# FMB-POWER.net
KiCad netlist of a schematic drawn in Altium Designer
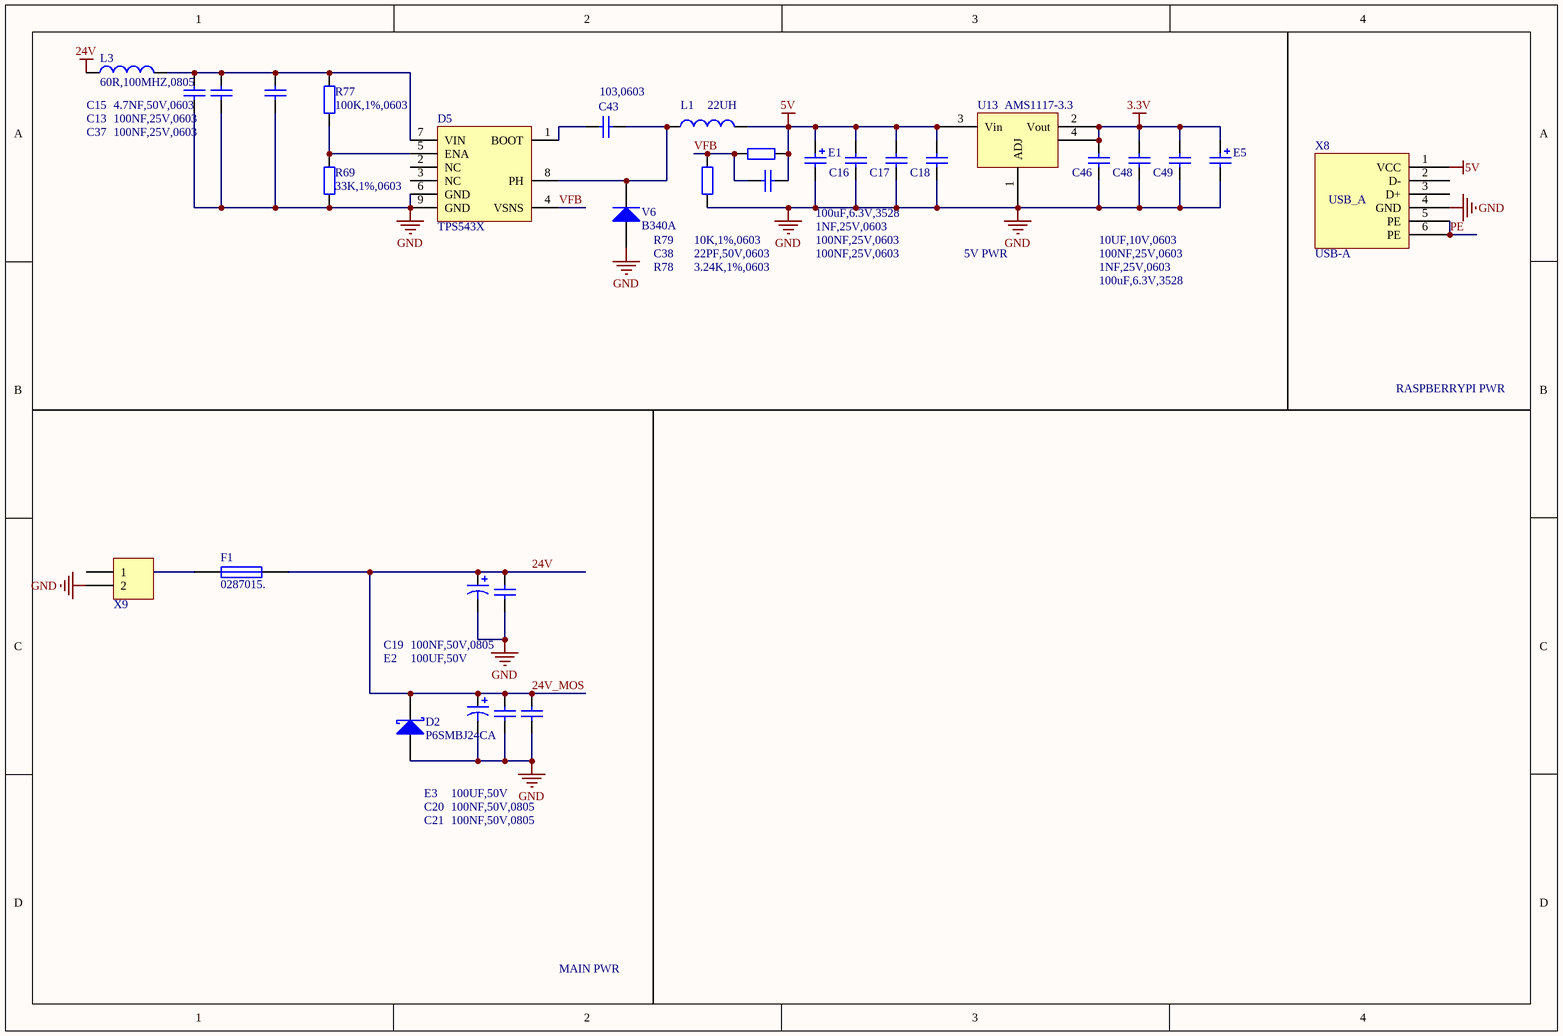
[diagram p0: FMB-POWER.SchDoc]

(export (version "E")
  (design (tool "Eeschema 10.0.6"))
  (components
    (comp (ref "C13")
      (value "100NF,25V,0603")
      (footprint "RC0603")
      (description "Capacitor")
      (fields (field (name "PUBLISHER") "Altium Limited"))
      (libsource (lib "Miscellaneous Devices") (part "Cap"))
    )
    (comp (ref "C15")
      (value "4.7NF,50V,0603")
      (footprint "RC0603")
      (description "Capacitor")
      (fields (field (name "PUBLISHER") "Altium Limited"))
      (libsource (lib "Miscellaneous Devices") (part "Cap"))
    )
    (comp (ref "C16")
      (value "1NF,25V,0603")
      (footprint "RC0603")
      (description "Capacitor")
      (fields (field (name "PUBLISHER") "Altium Limited"))
      (libsource (lib "Miscellaneous Devices") (part "Cap"))
    )
    (comp (ref "C17")
      (value "100NF,25V,0603")
      (footprint "RC0603")
      (description "Capacitor")
      (fields (field (name "PUBLISHER") "Altium Limited"))
      (libsource (lib "Miscellaneous Devices") (part "Cap"))
    )
    (comp (ref "C18")
      (value "100NF,25V,0603")
      (footprint "RC0603")
      (description "Capacitor")
      (fields (field (name "PUBLISHER") "Altium Limited"))
      (libsource (lib "Miscellaneous Devices") (part "Cap"))
    )
    (comp (ref "C19")
      (value "100NF,50V,0805")
      (footprint "RC0805")
      (description "Capacitor")
      (fields (field (name "PUBLISHER") "Altium Limited"))
      (libsource (lib "Miscellaneous Devices") (part "Cap"))
    )
    (comp (ref "C20")
      (value "100NF,50V,0805")
      (footprint "RC0805")
      (description "Capacitor")
      (fields (field (name "PUBLISHER") "Altium Limited"))
      (libsource (lib "Miscellaneous Devices") (part "Cap"))
    )
    (comp (ref "C21")
      (value "100NF,50V,0805")
      (footprint "RC0805")
      (description "Capacitor")
      (fields (field (name "PUBLISHER") "Altium Limited"))
      (libsource (lib "Miscellaneous Devices") (part "Cap"))
    )
    (comp (ref "C37")
      (value "100NF,25V,0603")
      (footprint "RC0603")
      (description "Capacitor")
      (fields (field (name "PUBLISHER") "Altium Limited"))
      (libsource (lib "Miscellaneous Devices") (part "Cap"))
    )
    (comp (ref "C38")
      (value "22PF,50V,0603")
      (footprint "RC0603")
      (description "Capacitor")
      (fields (field (name "PUBLISHER") "Altium Limited"))
      (libsource (lib "Miscellaneous Devices") (part "Cap"))
    )
    (comp (ref "C43")
      (value "103,0603")
      (footprint "RC0603")
      (description "Capacitor")
      (fields (field (name "PUBLISHER") "Altium Limited"))
      (libsource (lib "Miscellaneous Devices") (part "Cap"))
    )
    (comp (ref "C46")
      (value "100NF,25V,0603")
      (footprint "RC0603")
      (description "Capacitor")
      (fields (field (name "PUBLISHER") "Altium Limited"))
      (libsource (lib "Miscellaneous Devices") (part "Cap"))
    )
    (comp (ref "C48")
      (value "10UF,10V,0603")
      (footprint "RC0603")
      (description "Capacitor")
      (fields (field (name "PUBLISHER") "Altium Limited"))
      (libsource (lib "Miscellaneous Devices") (part "Cap"))
    )
    (comp (ref "C49")
      (value "1NF,25V,0603")
      (footprint "RC0603")
      (description "Capacitor")
      (fields (field (name "PUBLISHER") "Altium Limited"))
      (libsource (lib "Miscellaneous Devices") (part "Cap"))
    )
    (comp (ref "D2")
      (value "P6SMBJ24CA")
      (footprint "SMB")
      (description "Schottky Diode")
      (fields (field (name "PUBLISHER") "Altium Limited"))
      (libsource (lib "Miscellaneous Devices") (part "D Schottky"))
    )
    (comp (ref "D5") (value "TPS543X") (footprint "SO-8-1") (libsource (lib "LDO原理图库") (part "TPS543X")))
    (comp (ref "E1")
      (value "100uF,6.3V,3528")
      (footprint "3528-21")
      (description "Polarized Capacitor (Axial)")
      (fields (field (name "PUBLISHER") "Altium Limited"))
      (libsource (lib "Miscellaneous Devices") (part "Cap Pol2"))
    )
    (comp (ref "E2")
      (value "100UF,50V")
      (footprint "RB-.2X.4")
      (description "Polarized Capacitor (Surface Mount)")
      (fields (field (name "PUBLISHER") "Altium Limited"))
      (libsource (lib "Miscellaneous Devices") (part "Cap Pol3"))
    )
    (comp (ref "E3")
      (value "100UF,50V")
      (footprint "RB-.2X.4")
      (description "Polarized Capacitor (Surface Mount)")
      (fields (field (name "PUBLISHER") "Altium Limited"))
      (libsource (lib "Miscellaneous Devices") (part "Cap Pol3"))
    )
    (comp (ref "E5")
      (value "100uF,6.3V,3528")
      (description "Polarized Capacitor (Axial)")
      (fields (field (name "PUBLISHER") "Altium Limited"))
      (libsource (lib "Miscellaneous Devices") (part "Cap Pol2"))
    )
    (comp (ref "F1")
      (value "0287015.")
      (footprint "GF-C40")
      (description "Fuse")
      (fields (field (name "PUBLISHER") "Altium Limited"))
      (libsource (lib "Miscellaneous Devices") (part "Fuse 1"))
    )
    (comp (ref "L1")
      (value "22UH")
      (footprint "L7*7")
      (description "Inductor")
      (fields (field (name "PUBLISHER") "Altium Limited"))
      (libsource (lib "Miscellaneous Devices") (part "Inductor"))
    )
    (comp (ref "L3")
      (value "60R,100MHZ,0805")
      (footprint "RC0805")
      (description "Inductor")
      (fields (field (name "PUBLISHER") "Altium Limited"))
      (libsource (lib "Miscellaneous Devices") (part "Inductor"))
    )
    (comp (ref "R69")
      (value "33K,1%,0603")
      (footprint "RC0603")
      (description "Resistor")
      (fields (field (name "PUBLISHER") "Altium Limited"))
      (libsource (lib "Miscellaneous Devices") (part "Res2"))
    )
    (comp (ref "R77")
      (value "100K,1%,0603")
      (footprint "RC0603")
      (description "Resistor")
      (fields (field (name "PUBLISHER") "Altium Limited"))
      (libsource (lib "Miscellaneous Devices") (part "Res2"))
    )
    (comp (ref "R78")
      (value "3.24K,1%,0603")
      (footprint "RC0603")
      (description "Resistor")
      (fields (field (name "PUBLISHER") "Altium Limited"))
      (libsource (lib "Miscellaneous Devices") (part "Res2"))
    )
    (comp (ref "R79")
      (value "10K,1%,0603")
      (footprint "RC0603")
      (description "Resistor")
      (fields (field (name "PUBLISHER") "Altium Limited"))
      (libsource (lib "") (part "Res2_1"))
    )
    (comp (ref "U13")
      (value "AMS1117-3.3")
      (footprint "SOT-223")
      (libsource (lib "AMS1117") (part "AMS1117-3.3"))
    )
    (comp (ref "V6")
      (value "B340A")
      (footprint "SMA")
      (description "Default Diode")
      (fields (field (name "PUBLISHER") "Altium Limited"))
      (libsource (lib "Miscellaneous Devices") (part "Diode"))
    )
    (comp (ref "X8") (value "USB-A") (footprint "USB-A180") (libsource (lib "LDO原理图库") (part "USB-A")))
    (comp (ref "X9")
      (value "Molex 151048-1206")
      (footprint "151048")
      (description "Header, 2-Pin")
      (fields (field (name "PUBLISHER") "Altium Limited"))
      (libsource (lib "Miscellaneous Connectors") (part "Header 2"))
    )
  )
  (nets
    (net (code "1") (name "/PE") (class "Default")
      (node (ref "X8") (pin "5") (pinfunction "PE_5") (pintype "passive"))
      (node (ref "X8") (pin "6") (pinfunction "PE_6") (pintype "passive"))
    )
    (net (code "2") (name "/VFB") (class "Default")
      (node (ref "C38") (pin "2") (pinfunction "2_2") (pintype "passive"))
      (node (ref "D5") (pin "4") (pinfunction "VSNS_4") (pintype "passive"))
      (node (ref "R78") (pin "1") (pinfunction "1_1") (pintype "passive"))
      (node (ref "R79") (pin "1") (pinfunction "1_1") (pintype "passive"))
    )
    (net (code "3") (name "3.3V") (class "Default")
      (node (ref "C46") (pin "2") (pinfunction "2_2") (pintype "passive"))
      (node (ref "C48") (pin "2") (pinfunction "2_2") (pintype "passive"))
      (node (ref "C49") (pin "2") (pinfunction "2_2") (pintype "passive"))
      (node (ref "E5") (pin "1") (pinfunction "1_1") (pintype "passive"))
      (node (ref "U13") (pin "2") (pinfunction "Vout_2") (pintype "passive"))
      (node (ref "U13") (pin "4") (pinfunction "4_4") (pintype "passive"))
    )
    (net (code "4") (name "5V") (class "Default")
      (node (ref "C16") (pin "2") (pinfunction "2_2") (pintype "passive"))
      (node (ref "C17") (pin "2") (pinfunction "2_2") (pintype "passive"))
      (node (ref "C18") (pin "2") (pinfunction "2_2") (pintype "passive"))
      (node (ref "C38") (pin "1") (pinfunction "1_1") (pintype "passive"))
      (node (ref "E1") (pin "1") (pinfunction "1_1") (pintype "passive"))
      (node (ref "L1") (pin "2") (pinfunction "2_2") (pintype "passive"))
      (node (ref "R79") (pin "2") (pinfunction "2_2") (pintype "passive"))
      (node (ref "U13") (pin "3") (pinfunction "Vin_3") (pintype "passive"))
      (node (ref "X8") (pin "1") (pinfunction "VCC_1") (pintype "passive"))
    )
    (net (code "5") (name "24V") (class "Default")
      (node (ref "C19") (pin "1") (pinfunction "1_1") (pintype "passive"))
      (node (ref "C20") (pin "1") (pinfunction "1_1") (pintype "passive"))
      (node (ref "C21") (pin "1") (pinfunction "1_1") (pintype "passive"))
      (node (ref "D2") (pin "2") (pinfunction "K_2") (pintype "passive"))
      (node (ref "E2") (pin "1") (pinfunction "1_1") (pintype "passive"))
      (node (ref "E3") (pin "1") (pinfunction "1_1") (pintype "passive"))
      (node (ref "F1") (pin "1") (pinfunction "1_1") (pintype "passive"))
      (node (ref "L3") (pin "1") (pinfunction "1_1") (pintype "passive"))
    )
    (net (code "6") (name "GND") (class "Default")
      (node (ref "C13") (pin "2") (pinfunction "2_2") (pintype "passive"))
      (node (ref "C15") (pin "1") (pinfunction "1_1") (pintype "passive"))
      (node (ref "C16") (pin "1") (pinfunction "1_1") (pintype "passive"))
      (node (ref "C17") (pin "1") (pinfunction "1_1") (pintype "passive"))
      (node (ref "C18") (pin "1") (pinfunction "1_1") (pintype "passive"))
      (node (ref "C19") (pin "2") (pinfunction "2_2") (pintype "passive"))
      (node (ref "C20") (pin "2") (pinfunction "2_2") (pintype "passive"))
      (node (ref "C21") (pin "2") (pinfunction "2_2") (pintype "passive"))
      (node (ref "C37") (pin "2") (pinfunction "2_2") (pintype "passive"))
      (node (ref "C46") (pin "1") (pinfunction "1_1") (pintype "passive"))
      (node (ref "C48") (pin "1") (pinfunction "1_1") (pintype "passive"))
      (node (ref "C49") (pin "1") (pinfunction "1_1") (pintype "passive"))
      (node (ref "D2") (pin "1") (pinfunction "A_1") (pintype "passive"))
      (node (ref "D5") (pin "6") (pinfunction "GND_6") (pintype "passive"))
      (node (ref "D5") (pin "9") (pinfunction "GND_9") (pintype "passive"))
      (node (ref "E1") (pin "2") (pinfunction "2_2") (pintype "passive"))
      (node (ref "E2") (pin "2") (pinfunction "2_2") (pintype "passive"))
      (node (ref "E3") (pin "2") (pinfunction "2_2") (pintype "passive"))
      (node (ref "E5") (pin "2") (pinfunction "2_2") (pintype "passive"))
      (node (ref "R69") (pin "2") (pinfunction "2_2") (pintype "passive"))
      (node (ref "R78") (pin "2") (pinfunction "2_2") (pintype "passive"))
      (node (ref "U13") (pin "1") (pinfunction "ADJ_1") (pintype "passive"))
      (node (ref "V6") (pin "1") (pinfunction "A_1") (pintype "passive"))
      (node (ref "X8") (pin "4") (pinfunction "GND_4") (pintype "passive"))
      (node (ref "X9") (pin "2") (pinfunction "2_2") (pintype "passive"))
    )
    (net (code "7") (name "Net-(D5-BOOT)") (class "Default")
      (node (ref "C43") (pin "2") (pinfunction "2_2") (pintype "passive"))
      (node (ref "D5") (pin "1") (pinfunction "BOOT_1") (pintype "passive"))
    )
    (net (code "8") (name "Net-(D5-ENA)") (class "Default")
      (node (ref "D5") (pin "5") (pinfunction "ENA_5") (pintype "passive"))
      (node (ref "R69") (pin "1") (pinfunction "1_1") (pintype "passive"))
      (node (ref "R77") (pin "2") (pinfunction "2_2") (pintype "passive"))
    )
    (net (code "9") (name "Net-(D5-PH)") (class "Default")
      (node (ref "C43") (pin "1") (pinfunction "1_1") (pintype "passive"))
      (node (ref "D5") (pin "8") (pinfunction "PH_8") (pintype "passive"))
      (node (ref "L1") (pin "1") (pinfunction "1_1") (pintype "passive"))
      (node (ref "V6") (pin "2") (pinfunction "K_2") (pintype "passive"))
    )
    (net (code "10") (name "Net-(D5-VIN)") (class "Default")
      (node (ref "C13") (pin "1") (pinfunction "1_1") (pintype "passive"))
      (node (ref "C15") (pin "2") (pinfunction "2_2") (pintype "passive"))
      (node (ref "C37") (pin "1") (pinfunction "1_1") (pintype "passive"))
      (node (ref "D5") (pin "7") (pinfunction "VIN_7") (pintype "passive"))
      (node (ref "L3") (pin "2") (pinfunction "2_2") (pintype "passive"))
      (node (ref "R77") (pin "1") (pinfunction "1_1") (pintype "passive"))
    )
    (net (code "11") (name "Net-(F1-Pad2)") (class "Default")
      (node (ref "F1") (pin "2") (pinfunction "2_2") (pintype "passive"))
      (node (ref "X9") (pin "1") (pinfunction "1_1") (pintype "passive"))
    )
    (net (code "12") (name "unconnected-(D5-NC-Pad2)") (class "Default")
      (node (ref "D5") (pin "2") (pinfunction "NC_2") (pintype "passive"))
    )
    (net (code "13") (name "unconnected-(D5-NC-Pad3)") (class "Default")
      (node (ref "D5") (pin "3") (pinfunction "NC_3") (pintype "passive"))
    )
    (net (code "14") (name "unconnected-(X8-D+-Pad3)") (class "Default")
      (node (ref "X8") (pin "3") (pinfunction "D+_3") (pintype "passive"))
    )
    (net (code "15") (name "unconnected-(X8-D--Pad2)") (class "Default")
      (node (ref "X8") (pin "2") (pinfunction "D-_2") (pintype "passive"))
    )
  )
)
